# darkgame-controller.net
KiCad netlist of a schematic drawn in EAGLE
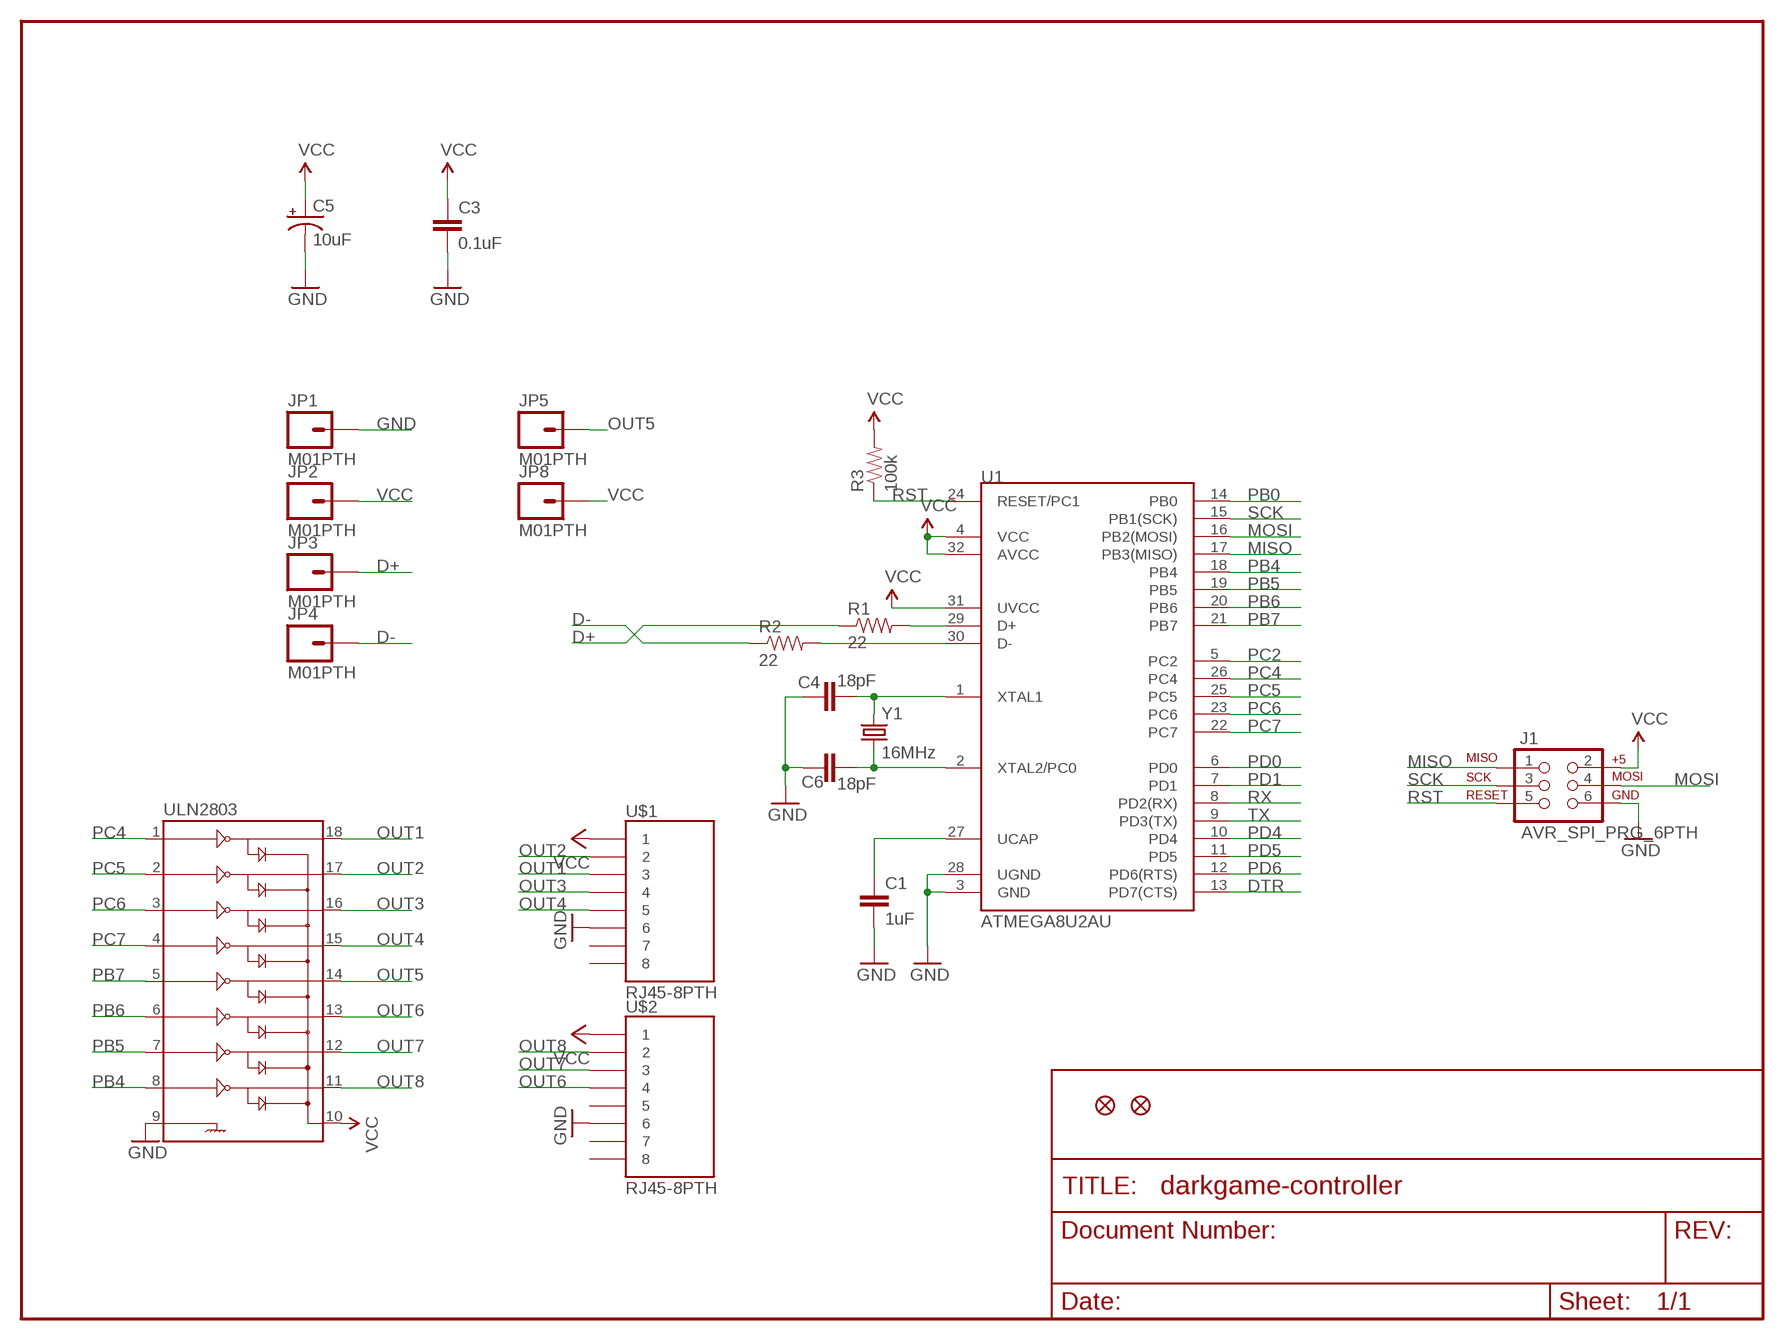
[diagram p0: schematic, sheet 1]

(export (version "E")
  (design (tool "Eeschema 10.0.6"))
  (components
    (comp (ref "C1")
      (value "1uF")
      (footprint "eagle-import:0805")
      (libsource (lib "eagle-import") (part "CAP0805"))
    )
    (comp (ref "C3")
      (value "0.1uF")
      (footprint "eagle-import:0805")
      (libsource (lib "eagle-import") (part "CAP0805"))
    )
    (comp (ref "C4")
      (value "18pF")
      (footprint "eagle-import:0805")
      (libsource (lib "eagle-import") (part "CAP0805"))
    )
    (comp (ref "C5")
      (value "10uF")
      (footprint "eagle-import:EIA3216")
      (libsource (lib "eagle-import") (part "CAP_POL1206"))
    )
    (comp (ref "C6")
      (value "18pF")
      (footprint "eagle-import:0805")
      (libsource (lib "eagle-import") (part "CAP0805"))
    )
    (comp (ref "J1")
      (value "AVR_SPI_PRG_6PTH")
      (footprint "eagle-import:2X3")
      (libsource (lib "eagle-import") (part "AVR_SPI_PRG_6PTH"))
    )
    (comp (ref "JP1")
      (value "M01PTH")
      (footprint "eagle-import:1X01")
      (libsource (lib "eagle-import") (part "M01PTH"))
    )
    (comp (ref "JP2")
      (value "M01PTH")
      (footprint "eagle-import:1X01")
      (libsource (lib "eagle-import") (part "M01PTH"))
    )
    (comp (ref "JP3")
      (value "M01PTH")
      (footprint "eagle-import:1X01")
      (libsource (lib "eagle-import") (part "M01PTH"))
    )
    (comp (ref "JP4")
      (value "M01PTH")
      (footprint "eagle-import:1X01")
      (libsource (lib "eagle-import") (part "M01PTH"))
    )
    (comp (ref "JP5")
      (value "M01PTH")
      (footprint "eagle-import:1X01")
      (libsource (lib "eagle-import") (part "M01PTH"))
    )
    (comp (ref "JP6")
      (value "FIDUCIAL1X2")
      (footprint "eagle-import:FIDUCIAL-1X2")
      (libsource (lib "eagle-import") (part "FIDUCIAL1X2"))
    )
    (comp (ref "JP7")
      (value "FIDUCIAL1X2")
      (footprint "eagle-import:FIDUCIAL-1X2")
      (libsource (lib "eagle-import") (part "FIDUCIAL1X2"))
    )
    (comp (ref "JP8")
      (value "M01PTH")
      (footprint "eagle-import:1X01")
      (libsource (lib "eagle-import") (part "M01PTH"))
    )
    (comp (ref "R1")
      (value "22")
      (footprint "eagle-import:0805")
      (libsource (lib "eagle-import") (part "RESISTOR0805-RES"))
    )
    (comp (ref "R2")
      (value "22")
      (footprint "eagle-import:0805")
      (libsource (lib "eagle-import") (part "RESISTOR0805-RES"))
    )
    (comp (ref "R3")
      (value "100k")
      (footprint "eagle-import:0805")
      (libsource (lib "eagle-import") (part "RESISTOR0805-RES"))
    )
    (comp (ref "U$1")
      (value "RJ45-8PTH")
      (footprint "eagle-import:RJ45-8")
      (libsource (lib "eagle-import") (part "RJ45-8PTH"))
    )
    (comp (ref "U$2")
      (value "RJ45-8PTH")
      (footprint "eagle-import:RJ45-8")
      (libsource (lib "eagle-import") (part "RJ45-8PTH"))
    )
    (comp (ref "U1")
      (value "ATMEGA8U2AU")
      (footprint "eagle-import:TQFP32-08")
      (libsource (lib "eagle-import") (part "ATMEGA8U2AU"))
    )
    (comp (ref "ULN2803")
      (value "ULN2803SOICW")
      (footprint "eagle-import:SO18L")
      (libsource (lib "eagle-import") (part "ULN2803SOICW"))
    )
    (comp (ref "Y1")
      (value "16MHz")
      (footprint "eagle-import:CRYSTAL-SMD-5X3")
      (libsource (lib "eagle-import") (part "CRYSTAL5X3"))
    )
  )
  (nets
    (net (code "1") (name "/D+") (class "Default")
      (node (ref "JP3") (pin "1") (pinfunction "1_1") (pintype "passive"))
      (node (ref "R1") (pin "1") (pinfunction "1_1") (pintype "passive"))
    )
    (net (code "2") (name "/D-") (class "Default")
      (node (ref "JP4") (pin "1") (pinfunction "1_1") (pintype "passive"))
      (node (ref "R2") (pin "1") (pinfunction "1_1") (pintype "passive"))
    )
    (net (code "3") (name "/DTR") (class "Default")
      (node (ref "U1") (pin "13") (pinfunction "PD7(CTS)_13") (pintype "bidirectional"))
    )
    (net (code "4") (name "/MISO") (class "Default")
      (node (ref "J1") (pin "1") (pinfunction "1_1") (pintype "passive"))
      (node (ref "U1") (pin "17") (pinfunction "PB3(MISO)_17") (pintype "bidirectional"))
    )
    (net (code "5") (name "/MOSI") (class "Default")
      (node (ref "J1") (pin "4") (pinfunction "4_4") (pintype "passive"))
      (node (ref "U1") (pin "16") (pinfunction "PB2(MOSI)_16") (pintype "bidirectional"))
    )
    (net (code "6") (name "/OUT1") (class "Default")
      (node (ref "U$1") (pin "3") (pinfunction "3_3") (pintype "bidirectional"))
      (node (ref "ULN2803") (pin "18") (pinfunction "18_18") (pintype "bidirectional"))
    )
    (net (code "7") (name "/OUT2") (class "Default")
      (node (ref "U$1") (pin "2") (pinfunction "2_2") (pintype "bidirectional"))
      (node (ref "ULN2803") (pin "17") (pinfunction "17_17") (pintype "bidirectional"))
    )
    (net (code "8") (name "/OUT3") (class "Default")
      (node (ref "U$1") (pin "4") (pinfunction "4_4") (pintype "bidirectional"))
      (node (ref "ULN2803") (pin "16") (pinfunction "16_16") (pintype "bidirectional"))
    )
    (net (code "9") (name "/OUT4") (class "Default")
      (node (ref "U$1") (pin "5") (pinfunction "5_5") (pintype "bidirectional"))
      (node (ref "ULN2803") (pin "15") (pinfunction "15_15") (pintype "bidirectional"))
    )
    (net (code "10") (name "/OUT5") (class "Default")
      (node (ref "JP5") (pin "1") (pinfunction "1_1") (pintype "passive"))
      (node (ref "ULN2803") (pin "14") (pinfunction "14_14") (pintype "bidirectional"))
    )
    (net (code "11") (name "/OUT6") (class "Default")
      (node (ref "U$2") (pin "4") (pinfunction "4_4") (pintype "bidirectional"))
      (node (ref "ULN2803") (pin "13") (pinfunction "13_13") (pintype "bidirectional"))
    )
    (net (code "12") (name "/OUT7") (class "Default")
      (node (ref "U$2") (pin "3") (pinfunction "3_3") (pintype "bidirectional"))
      (node (ref "ULN2803") (pin "12") (pinfunction "12_12") (pintype "bidirectional"))
    )
    (net (code "13") (name "/OUT8") (class "Default")
      (node (ref "U$2") (pin "2") (pinfunction "2_2") (pintype "bidirectional"))
      (node (ref "ULN2803") (pin "11") (pinfunction "11_11") (pintype "bidirectional"))
    )
    (net (code "14") (name "/PB0") (class "Default")
      (node (ref "U1") (pin "14") (pinfunction "PB0_14") (pintype "bidirectional"))
    )
    (net (code "15") (name "/PB4") (class "Default")
      (node (ref "U1") (pin "18") (pinfunction "PB4_18") (pintype "bidirectional"))
      (node (ref "ULN2803") (pin "8") (pinfunction "8_8") (pintype "bidirectional"))
    )
    (net (code "16") (name "/PB5") (class "Default")
      (node (ref "U1") (pin "19") (pinfunction "PB5_19") (pintype "bidirectional"))
      (node (ref "ULN2803") (pin "7") (pinfunction "7_7") (pintype "bidirectional"))
    )
    (net (code "17") (name "/PB6") (class "Default")
      (node (ref "U1") (pin "20") (pinfunction "PB6_20") (pintype "bidirectional"))
      (node (ref "ULN2803") (pin "6") (pinfunction "6_6") (pintype "bidirectional"))
    )
    (net (code "18") (name "/PB7") (class "Default")
      (node (ref "U1") (pin "21") (pinfunction "PB7_21") (pintype "bidirectional"))
      (node (ref "ULN2803") (pin "5") (pinfunction "5_5") (pintype "bidirectional"))
    )
    (net (code "19") (name "/PC2") (class "Default")
      (node (ref "U1") (pin "5") (pinfunction "PC2_5") (pintype "bidirectional"))
    )
    (net (code "20") (name "/PC4") (class "Default")
      (node (ref "U1") (pin "26") (pinfunction "PC4_26") (pintype "bidirectional"))
      (node (ref "ULN2803") (pin "1") (pinfunction "1_1") (pintype "bidirectional"))
    )
    (net (code "21") (name "/PC5") (class "Default")
      (node (ref "U1") (pin "25") (pinfunction "PC5_25") (pintype "bidirectional"))
      (node (ref "ULN2803") (pin "2") (pinfunction "2_2") (pintype "bidirectional"))
    )
    (net (code "22") (name "/PC6") (class "Default")
      (node (ref "U1") (pin "23") (pinfunction "PC6_23") (pintype "bidirectional"))
      (node (ref "ULN2803") (pin "3") (pinfunction "3_3") (pintype "bidirectional"))
    )
    (net (code "23") (name "/PC7") (class "Default")
      (node (ref "U1") (pin "22") (pinfunction "PC7_22") (pintype "bidirectional"))
      (node (ref "ULN2803") (pin "4") (pinfunction "4_4") (pintype "bidirectional"))
    )
    (net (code "24") (name "/PD0") (class "Default")
      (node (ref "U1") (pin "6") (pinfunction "PD0_6") (pintype "bidirectional"))
    )
    (net (code "25") (name "/PD1") (class "Default")
      (node (ref "U1") (pin "7") (pinfunction "PD1_7") (pintype "bidirectional"))
    )
    (net (code "26") (name "/PD4") (class "Default")
      (node (ref "U1") (pin "10") (pinfunction "PD4_10") (pintype "bidirectional"))
    )
    (net (code "27") (name "/PD5") (class "Default")
      (node (ref "U1") (pin "11") (pinfunction "PD5_11") (pintype "bidirectional"))
    )
    (net (code "28") (name "/PD6") (class "Default")
      (node (ref "U1") (pin "12") (pinfunction "PD6(RTS)_12") (pintype "bidirectional"))
    )
    (net (code "29") (name "/RST") (class "Default")
      (node (ref "J1") (pin "5") (pinfunction "5_5") (pintype "passive"))
      (node (ref "R3") (pin "1") (pinfunction "1_1") (pintype "passive"))
      (node (ref "U1") (pin "24") (pinfunction "RESET/PC1_24") (pintype "bidirectional"))
    )
    (net (code "30") (name "/RX") (class "Default")
      (node (ref "U1") (pin "8") (pinfunction "PD2(RX)_8") (pintype "bidirectional"))
    )
    (net (code "31") (name "/SCK") (class "Default")
      (node (ref "J1") (pin "3") (pinfunction "3_3") (pintype "passive"))
      (node (ref "U1") (pin "15") (pinfunction "PB1(SCK)_15") (pintype "bidirectional"))
    )
    (net (code "32") (name "/TX") (class "Default")
      (node (ref "U1") (pin "9") (pinfunction "PD3(TX)_9") (pintype "bidirectional"))
    )
    (net (code "33") (name "GND") (class "Default")
      (node (ref "C1") (pin "2") (pinfunction "2_2") (pintype "passive"))
      (node (ref "C3") (pin "2") (pinfunction "2_2") (pintype "passive"))
      (node (ref "C4") (pin "2") (pinfunction "2_2") (pintype "passive"))
      (node (ref "C5") (pin "C") (pinfunction "-_C") (pintype "passive"))
      (node (ref "C6") (pin "2") (pinfunction "2_2") (pintype "passive"))
      (node (ref "J1") (pin "6") (pinfunction "6_6") (pintype "passive"))
      (node (ref "JP1") (pin "1") (pinfunction "1_1") (pintype "passive"))
      (node (ref "U$1") (pin "6") (pinfunction "6_6") (pintype "bidirectional"))
      (node (ref "U$2") (pin "6") (pinfunction "6_6") (pintype "bidirectional"))
      (node (ref "U1") (pin "28") (pinfunction "UGND_28") (pintype "bidirectional"))
      (node (ref "U1") (pin "3") (pinfunction "GND_3") (pintype "bidirectional"))
      (node (ref "ULN2803") (pin "9") (pinfunction "9_9") (pintype "bidirectional"))
    )
    (net (code "34") (name "Net-(U1-D+)") (class "Default")
      (node (ref "R1") (pin "2") (pinfunction "2_2") (pintype "passive"))
      (node (ref "U1") (pin "29") (pinfunction "D+_29") (pintype "bidirectional"))
    )
    (net (code "35") (name "Net-(U1-D-)") (class "Default")
      (node (ref "R2") (pin "2") (pinfunction "2_2") (pintype "passive"))
      (node (ref "U1") (pin "30") (pinfunction "D-_30") (pintype "bidirectional"))
    )
    (net (code "36") (name "Net-(U1-UCAP)") (class "Default")
      (node (ref "C1") (pin "1") (pinfunction "1_1") (pintype "passive"))
      (node (ref "U1") (pin "27") (pinfunction "UCAP_27") (pintype "bidirectional"))
    )
    (net (code "37") (name "Net-(U1-XTAL1)") (class "Default")
      (node (ref "C4") (pin "1") (pinfunction "1_1") (pintype "passive"))
      (node (ref "U1") (pin "1") (pinfunction "XTAL1_1") (pintype "bidirectional"))
      (node (ref "Y1") (pin "3") (pinfunction "2_3") (pintype "passive"))
    )
    (net (code "38") (name "Net-(U1-XTAL2{slash}PC0)") (class "Default")
      (node (ref "C6") (pin "1") (pinfunction "1_1") (pintype "passive"))
      (node (ref "U1") (pin "2") (pinfunction "XTAL2/PC0_2") (pintype "bidirectional"))
      (node (ref "Y1") (pin "1") (pinfunction "1_1") (pintype "passive"))
    )
    (net (code "39") (name "VCC") (class "Default")
      (node (ref "C3") (pin "1") (pinfunction "1_1") (pintype "passive"))
      (node (ref "C5") (pin "A") (pinfunction "+_A") (pintype "passive"))
      (node (ref "J1") (pin "2") (pinfunction "2_2") (pintype "passive"))
      (node (ref "JP2") (pin "1") (pinfunction "1_1") (pintype "passive"))
      (node (ref "JP8") (pin "1") (pinfunction "1_1") (pintype "passive"))
      (node (ref "R3") (pin "2") (pinfunction "2_2") (pintype "passive"))
      (node (ref "U$1") (pin "1") (pinfunction "1_1") (pintype "bidirectional"))
      (node (ref "U$2") (pin "1") (pinfunction "1_1") (pintype "bidirectional"))
      (node (ref "U1") (pin "31") (pinfunction "UVCC_31") (pintype "bidirectional"))
      (node (ref "U1") (pin "32") (pinfunction "AVCC_32") (pintype "bidirectional"))
      (node (ref "U1") (pin "4") (pinfunction "VCC_4") (pintype "bidirectional"))
      (node (ref "ULN2803") (pin "10") (pinfunction "10_10") (pintype "bidirectional"))
    )
    (net (code "40") (name "unconnected-(U$1-Pad7)") (class "Default")
      (node (ref "U$1") (pin "7") (pinfunction "7_7") (pintype "bidirectional"))
    )
    (net (code "41") (name "unconnected-(U$1-Pad8)") (class "Default")
      (node (ref "U$1") (pin "8") (pinfunction "8_8") (pintype "bidirectional"))
    )
    (net (code "42") (name "unconnected-(U$2-Pad5)") (class "Default")
      (node (ref "U$2") (pin "5") (pinfunction "5_5") (pintype "bidirectional"))
    )
    (net (code "43") (name "unconnected-(U$2-Pad7)") (class "Default")
      (node (ref "U$2") (pin "7") (pinfunction "7_7") (pintype "bidirectional"))
    )
    (net (code "44") (name "unconnected-(U$2-Pad8)") (class "Default")
      (node (ref "U$2") (pin "8") (pinfunction "8_8") (pintype "bidirectional"))
    )
  )
)
